# 01_POWER.net
KiCad netlist of a schematic drawn in Altium Designer
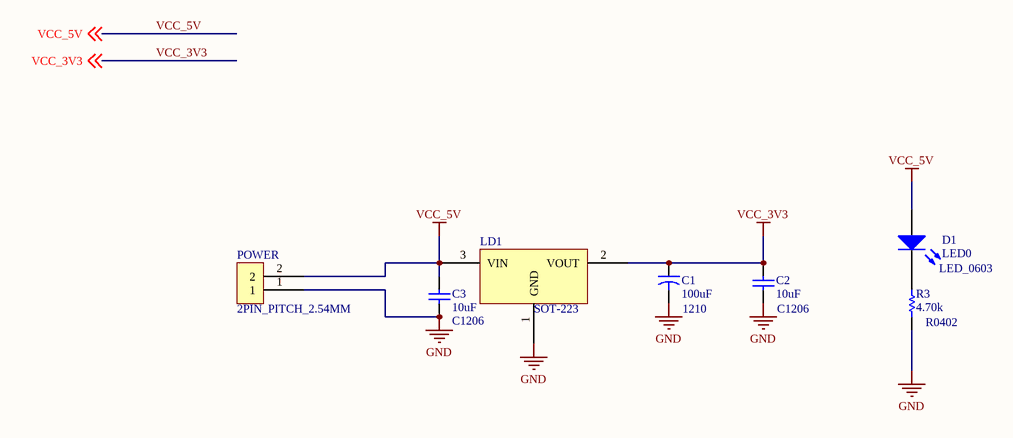
[diagram p0: 01 POWER.SchDoc]

(export (version "E")
  (design (tool "Eeschema 10.0.6"))
  (components
    (comp (ref "C1")
      (value "100uF")
      (footprint "1210")
      (description "Capacitor")
      (fields (field (name "PUBLISHER") "Altium Limited"))
      (libsource (lib "Miscellaneous Devices") (part "Cap2"))
    )
    (comp (ref "C2")
      (value "10uF")
      (footprint "C1206")
      (description "Capacitor")
      (fields (field (name "PUBLISHER") "Altium Limited"))
      (libsource (lib "Miscellaneous Devices") (part "Cap"))
    )
    (comp (ref "C3")
      (value "10uF")
      (footprint "C1206")
      (description "Capacitor")
      (fields (field (name "PUBLISHER") "Altium Limited"))
      (libsource (lib "Miscellaneous Devices") (part "Cap"))
    )
    (comp (ref "D1")
      (value "LED0")
      (footprint "LED_0603")
      (description "Typical INFRARED GaAs LED")
      (fields (field (name "FOOTPRIINT") "LED_0603") (field (name "PUBLISHER") "Altium Limited"))
      (libsource (lib "Miscellaneous Devices") (part "LED0"))
    )
    (comp (ref "LD1")
      (value "SOT-223")
      (footprint "LD1117S33TR")
      (libsource (lib "Integrated_Library") (part "LD1117S33TR"))
    )
    (comp (ref "POWER")
      (value "2PIN_PITCH_2.54MM")
      (footprint "2PIN_PITCH_2.54MM")
      (libsource (lib "Integrated_Library") (part "2PIN_PITCH_2.54MM"))
    )
    (comp (ref "R3")
      (value "4.70k")
      (footprint "R0402")
      (description "Resistor")
      (fields (field (name "PUBLISHER") "Altium Limited"))
      (libsource (lib "Miscellaneous Devices") (part "Res1"))
    )
  )
  (nets
    (net (code "1") (name "GND") (class "Default")
      (node (ref "C1") (pin "2") (pinfunction "2_2") (pintype "passive"))
      (node (ref "C2") (pin "1") (pinfunction "1_1") (pintype "passive"))
      (node (ref "C3") (pin "1") (pinfunction "1_1") (pintype "passive"))
      (node (ref "LD1") (pin "1") (pinfunction "GND_1") (pintype "passive"))
      (node (ref "POWER") (pin "1") (pinfunction "1_1") (pintype "passive"))
      (node (ref "R3") (pin "2") (pinfunction "2_2") (pintype "passive"))
    )
    (net (code "2") (name "Net-(D1-K)") (class "Default")
      (node (ref "D1") (pin "2") (pinfunction "K_2") (pintype "passive"))
      (node (ref "R3") (pin "1") (pinfunction "1_1") (pintype "passive"))
    )
    (net (code "3") (name "VCC_3V3") (class "Default")
      (node (ref "C1") (pin "1") (pinfunction "1_1") (pintype "passive"))
      (node (ref "C2") (pin "2") (pinfunction "2_2") (pintype "passive"))
      (node (ref "LD1") (pin "2") (pinfunction "VOUT_2") (pintype "passive"))
    )
    (net (code "4") (name "VCC_5V") (class "Default")
      (node (ref "C3") (pin "2") (pinfunction "2_2") (pintype "passive"))
      (node (ref "D1") (pin "1") (pinfunction "A_1") (pintype "passive"))
      (node (ref "LD1") (pin "3") (pinfunction "VIN_3") (pintype "passive"))
      (node (ref "POWER") (pin "2") (pinfunction "2_2") (pintype "passive"))
    )
  )
)
